# overview_mcu.net
KiCad netlist of a schematic drawn in EAGLE
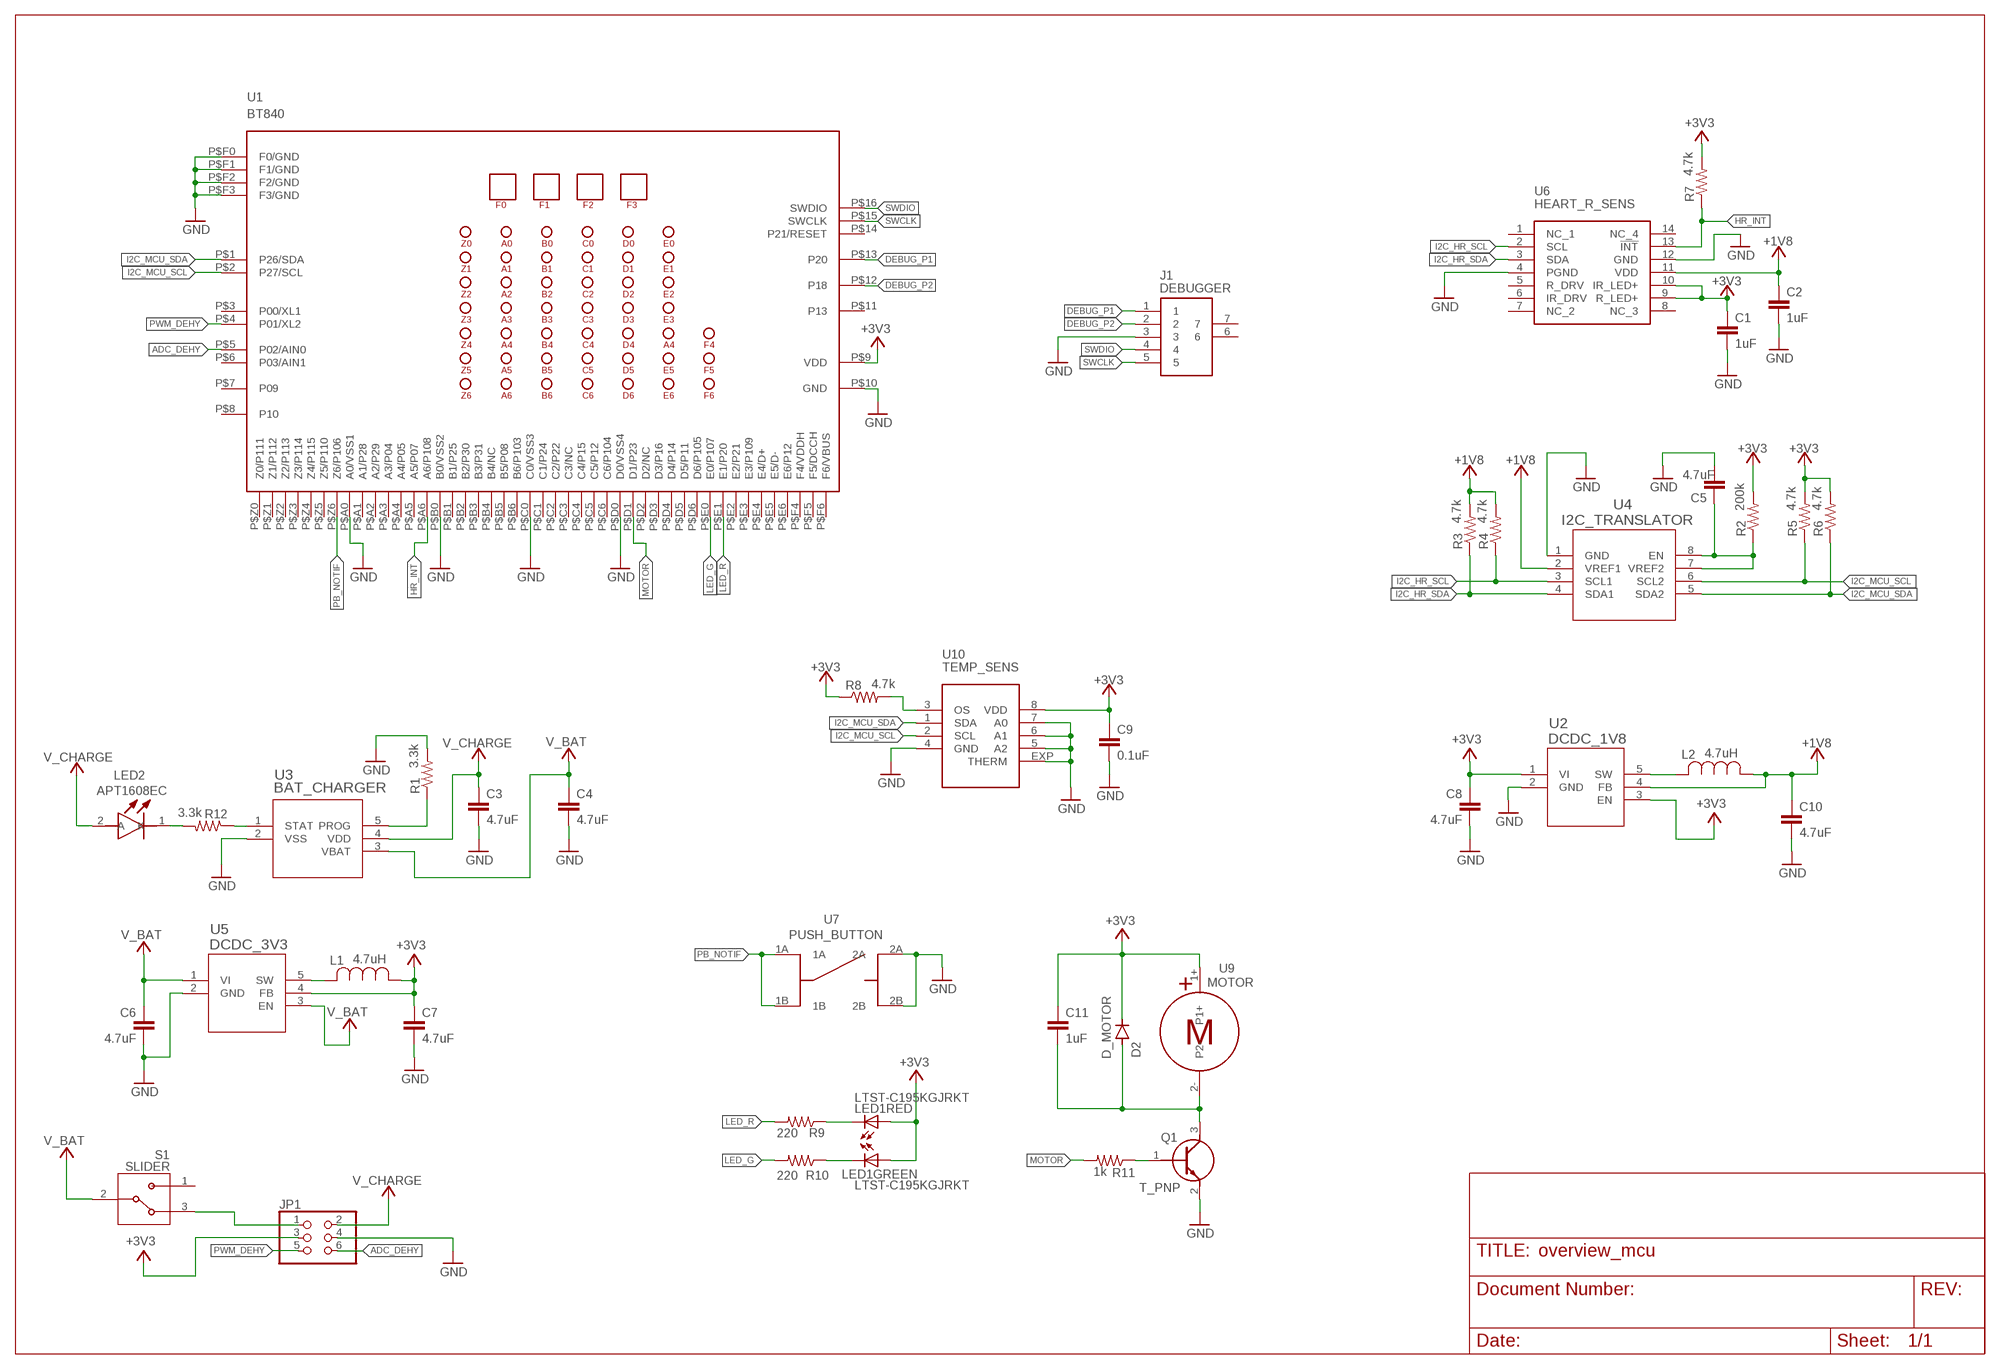
[diagram p0: schematic, sheet 1]

(export (version "E")
  (design (tool "Eeschema 10.0.6"))
  (components
    (comp (ref "C1")
      (value "1uF")
      (footprint "eagle-import:C0402K")
      (libsource (lib "eagle-import") (part "C-EUC0402K"))
    )
    (comp (ref "C2")
      (value "1uF")
      (footprint "eagle-import:C0402K")
      (libsource (lib "eagle-import") (part "C-EUC0402K"))
    )
    (comp (ref "C3")
      (value "4.7uF")
      (footprint "eagle-import:C0402K")
      (libsource (lib "eagle-import") (part "C-EUC0402K"))
    )
    (comp (ref "C4")
      (value "4.7uF")
      (footprint "eagle-import:C0402K")
      (libsource (lib "eagle-import") (part "C-EUC0402K"))
    )
    (comp (ref "C5")
      (value "4.7uF")
      (footprint "eagle-import:C0402K")
      (libsource (lib "eagle-import") (part "C-EUC0402K"))
    )
    (comp (ref "C6")
      (value "4.7uF")
      (footprint "eagle-import:C0402K")
      (libsource (lib "eagle-import") (part "C-EUC0402K"))
    )
    (comp (ref "C7")
      (value "4.7uF")
      (footprint "eagle-import:C0402K")
      (libsource (lib "eagle-import") (part "C-EUC0402K"))
    )
    (comp (ref "C8")
      (value "4.7uF")
      (footprint "eagle-import:C0402K")
      (libsource (lib "eagle-import") (part "C-EUC0402K"))
    )
    (comp (ref "C9")
      (value "0.1uF")
      (footprint "eagle-import:C0402K")
      (libsource (lib "eagle-import") (part "C-EUC0402K"))
    )
    (comp (ref "C10")
      (value "4.7uF")
      (footprint "eagle-import:C0402K")
      (libsource (lib "eagle-import") (part "C-EUC0402K"))
    )
    (comp (ref "C11")
      (value "1uF")
      (footprint "eagle-import:C0402K")
      (libsource (lib "eagle-import") (part "C-EUC0402K"))
    )
    (comp (ref "D2")
      (value "D_MOTOR")
      (footprint "eagle-import:SOD-123_MINI-SMA")
      (libsource (lib "eagle-import") (part "CGRM400-G1"))
    )
    (comp (ref "J1")
      (value "DEBUGGER")
      (footprint "eagle-import:0512810594")
      (fields (field (name "MANUFACTURER_PART_NUM") "0512810594"))
      (libsource (lib "eagle-import") (part "DEBUGGER"))
    )
    (comp (ref "JP1")
      (value "PINHD-2X3")
      (footprint "eagle-import:2X03")
      (libsource (lib "eagle-import") (part "PINHD-2X3"))
    )
    (comp (ref "L1")
      (value "4.7uH")
      (footprint "eagle-import:IND_1608")
      (fields (field (name "MANUFACTURER_PART_NUMBER") "GLFR1608T4R7MLR"))
      (libsource (lib "eagle-import") (part "L_0604"))
    )
    (comp (ref "L2")
      (value "4.7uH")
      (footprint "eagle-import:IND_1608")
      (fields (field (name "MANUFACTURER_PART_NUMBER") "GLFR1608T4R7MLR"))
      (libsource (lib "eagle-import") (part "L_0604"))
    )
    (comp (ref "LED1")
      (value "LTST-C195KGJRKT")
      (footprint "eagle-import:LED-SMT")
      (fields
        (field (name "MANUFACTURER") "Lite-On Inc.")
        (field (name "MANUFACTURER_PART_NUM") "LTST-C195KGJRKT ")
      )
      (libsource (lib "eagle-import") (part "LTST-C195KGJRKT"))
    )
    (comp (ref "LED2")
      (value "APT1608EC")
      (footprint "eagle-import:LEDC1608X85N")
      (fields (field (name "MANUFACTURER") "Kingbright"))
      (libsource (lib "eagle-import") (part "APT1608EC"))
    )
    (comp (ref "Q1")
      (value "T_PNP")
      (footprint "eagle-import:SOT95P240X93-3N")
      (fields
        (field (name "MANUFACTURER") "Micro Commercial Co")
        (field (name "MANUFACTURER_PART_NUM") "MMBT3904-TP ")
      )
      (libsource (lib "eagle-import") (part "T_PNP"))
    )
    (comp (ref "R1")
      (value "3.3k")
      (footprint "eagle-import:R0402")
      (libsource (lib "eagle-import") (part "R-US_R0402"))
    )
    (comp (ref "R2")
      (value "200k")
      (footprint "eagle-import:R0402")
      (libsource (lib "eagle-import") (part "R-US_R0402"))
    )
    (comp (ref "R3")
      (value "4.7k")
      (footprint "eagle-import:R0402")
      (libsource (lib "eagle-import") (part "R-US_R0402"))
    )
    (comp (ref "R4")
      (value "4.7k")
      (footprint "eagle-import:R0402")
      (libsource (lib "eagle-import") (part "R-US_R0402"))
    )
    (comp (ref "R5")
      (value "4.7k")
      (footprint "eagle-import:R0402")
      (libsource (lib "eagle-import") (part "R-US_R0402"))
    )
    (comp (ref "R6")
      (value "4.7k")
      (footprint "eagle-import:R0402")
      (libsource (lib "eagle-import") (part "R-US_R0402"))
    )
    (comp (ref "R7")
      (value "4.7k")
      (footprint "eagle-import:R0402")
      (libsource (lib "eagle-import") (part "R-US_R0402"))
    )
    (comp (ref "R8")
      (value "4.7k")
      (footprint "eagle-import:R0402")
      (libsource (lib "eagle-import") (part "R-US_R0402"))
    )
    (comp (ref "R9")
      (value "220")
      (footprint "eagle-import:R0402")
      (libsource (lib "eagle-import") (part "R-US_R0402"))
    )
    (comp (ref "R10")
      (value "220")
      (footprint "eagle-import:R0402")
      (libsource (lib "eagle-import") (part "R-US_R0402"))
    )
    (comp (ref "R11")
      (value "1k")
      (footprint "eagle-import:R0402")
      (libsource (lib "eagle-import") (part "R-US_R0402"))
    )
    (comp (ref "R12")
      (value "3.3k")
      (footprint "eagle-import:R0402")
      (libsource (lib "eagle-import") (part "R-US_R0402"))
    )
    (comp (ref "S1")
      (value "SLIDER")
      (footprint "eagle-import:SW_CJS-1200TA")
      (fields
        (field (name "MANUFACTURER") "Nidec Copal Electronics")
        (field (name "MANUFACTURER_PART") "CJS-1200TA ")
      )
      (libsource (lib "eagle-import") (part "SLIDER"))
    )
    (comp (ref "U1")
      (value "BT840")
      (footprint "eagle-import:BT840")
      (fields (field (name "MANUFACTURER") "Fanstel"))
      (libsource (lib "eagle-import") (part "BT840"))
    )
    (comp (ref "U2")
      (value "DCDC_1V8")
      (footprint "eagle-import:DBV5")
      (fields
        (field (name "MANUFACTURER") "Texas Instruments")
        (field (name "MANUFACTURER_PART_NUM") "TPS62202DBVR")
      )
      (libsource (lib "eagle-import") (part "DCDC_1V8"))
    )
    (comp (ref "U3")
      (value "BAT_CHARGER")
      (footprint "eagle-import:SOT-23-5_MC")
      (fields
        (field (name "MANUFACTURER") "Microchip")
        (field (name "MANUFACTURER_PART_NUM") "MCP73831T2ACIOT")
      )
      (libsource (lib "eagle-import") (part "BAT_CHARGER"))
    )
    (comp (ref "U4")
      (value "I2C_TRANSLATOR")
      (footprint "eagle-import:DQE8")
      (fields
        (field (name "MANUFACTURER") "Texas Instruments")
        (field (name "MANUFACTURER_PART_NUM") "PCA9306DQER")
      )
      (libsource (lib "eagle-import") (part "I2C_TRANSLATOR"))
    )
    (comp (ref "U5")
      (value "DCDC_3V3")
      (footprint "eagle-import:DBV5")
      (fields
        (field (name "MANUFACTURER") "Texas Instruments")
        (field (name "MANUFACTURER_PART_NUM") "TPS62203DBVR")
      )
      (libsource (lib "eagle-import") (part "DCDC_3V3"))
    )
    (comp (ref "U6")
      (value "HEART_R_SENS")
      (footprint "eagle-import:MAX30102")
      (fields
        (field (name "MANUFACTURER") "Maxim Integrated")
        (field (name "MANUFACTURER_PART_NUM") "MAX30102EFD+")
      )
      (libsource (lib "eagle-import") (part "HEART_R_SENS"))
    )
    (comp (ref "U7")
      (value "PUSH_BUTTON")
      (footprint "eagle-import:PUSH_BUTTON")
      (fields
        (field (name "MANUFACTURER") " Panasonic Electronic Components")
        (field (name "MANUFACTURER_PART_NUM") "EVQ-P7A01P ")
      )
      (libsource (lib "eagle-import") (part "PUSH_BUTTON"))
    )
    (comp (ref "U9")
      (value "MOTOR")
      (footprint "eagle-import:MOTOR")
      (fields
        (field (name "MANUFACTURER") "Jinlong Machinery & Electronics, Inc.")
        (field (name "MANUFACTURER_PART_NUM") "Z4FC1B1301781")
      )
      (libsource (lib "eagle-import") (part "MOTOR"))
    )
    (comp (ref "U10")
      (value "TEMP_SENS")
      (footprint "eagle-import:MAX30205")
      (fields
        (field (name "MANUFACTURER") "Maxim Integrated")
        (field (name "MANUFACTURER_PART_NUM") "MAX30205MTA+")
      )
      (libsource (lib "eagle-import") (part "TEMP_SENS"))
    )
  )
  (nets
    (net (code "1") (name "+1V8") (class "Default")
      (node (ref "C10") (pin "1") (pinfunction "1_1") (pintype "passive"))
      (node (ref "C2") (pin "1") (pinfunction "1_1") (pintype "passive"))
      (node (ref "L2") (pin "1") (pinfunction "1_1") (pintype "passive"))
      (node (ref "R3") (pin "2") (pinfunction "2_2") (pintype "passive"))
      (node (ref "R4") (pin "2") (pinfunction "2_2") (pintype "passive"))
      (node (ref "U2") (pin "4") (pinfunction "FB_4") (pintype "input"))
      (node (ref "U4") (pin "2") (pinfunction "VREF1_2") (pintype "passive"))
      (node (ref "U6") (pin "11") (pinfunction "VDD_11") (pintype "bidirectional"))
    )
    (net (code "2") (name "+3V3") (class "Default")
      (node (ref "C1") (pin "1") (pinfunction "1_1") (pintype "passive"))
      (node (ref "C11") (pin "1") (pinfunction "1_1") (pintype "passive"))
      (node (ref "C7") (pin "1") (pinfunction "1_1") (pintype "passive"))
      (node (ref "C8") (pin "1") (pinfunction "1_1") (pintype "passive"))
      (node (ref "C9") (pin "1") (pinfunction "1_1") (pintype "passive"))
      (node (ref "D2") (pin "C") (pinfunction "C_C") (pintype "passive"))
      (node (ref "JP1") (pin "3") (pinfunction "3_3") (pintype "passive"))
      (node (ref "L1") (pin "1") (pinfunction "1_1") (pintype "passive"))
      (node (ref "LED1") (pin "P$1") (pinfunction "A_P$1") (pintype "passive"))
      (node (ref "LED1") (pin "P$2") (pinfunction "A_P$2") (pintype "passive"))
      (node (ref "R2") (pin "2") (pinfunction "2_2") (pintype "passive"))
      (node (ref "R5") (pin "2") (pinfunction "2_2") (pintype "passive"))
      (node (ref "R6") (pin "2") (pinfunction "2_2") (pintype "passive"))
      (node (ref "R7") (pin "2") (pinfunction "2_2") (pintype "passive"))
      (node (ref "R8") (pin "1") (pinfunction "1_1") (pintype "passive"))
      (node (ref "U1") (pin "P$9") (pinfunction "VDD_P$9") (pintype "bidirectional"))
      (node (ref "U10") (pin "8") (pinfunction "VDD_8") (pintype "bidirectional"))
      (node (ref "U2") (pin "1") (pinfunction "VI_1") (pintype "input"))
      (node (ref "U2") (pin "3") (pinfunction "EN_3") (pintype "input"))
      (node (ref "U5") (pin "4") (pinfunction "FB_4") (pintype "input"))
      (node (ref "U6") (pin "10") (pinfunction "IR_LED+_10") (pintype "bidirectional"))
      (node (ref "U6") (pin "9") (pinfunction "R_LED+_9") (pintype "bidirectional"))
      (node (ref "U9") (pin "1+") (pinfunction "P1+_1+") (pintype "bidirectional"))
    )
    (net (code "3") (name "ADC_DEHY") (class "Default")
      (node (ref "JP1") (pin "6") (pinfunction "6_6") (pintype "passive"))
      (node (ref "U1") (pin "P$5") (pinfunction "P02/AIN0_P$5") (pintype "bidirectional"))
    )
    (net (code "4") (name "DEBUG_P1") (class "Default")
      (node (ref "J1") (pin "1") (pinfunction "1_1") (pintype "bidirectional"))
      (node (ref "U1") (pin "P$13") (pinfunction "P20_P$13") (pintype "bidirectional"))
    )
    (net (code "5") (name "DEBUG_P2") (class "Default")
      (node (ref "J1") (pin "2") (pinfunction "2_2") (pintype "bidirectional"))
      (node (ref "U1") (pin "P$12") (pinfunction "P18_P$12") (pintype "bidirectional"))
    )
    (net (code "6") (name "GND") (class "Default")
      (node (ref "C1") (pin "2") (pinfunction "2_2") (pintype "passive"))
      (node (ref "C10") (pin "2") (pinfunction "2_2") (pintype "passive"))
      (node (ref "C2") (pin "2") (pinfunction "2_2") (pintype "passive"))
      (node (ref "C3") (pin "2") (pinfunction "2_2") (pintype "passive"))
      (node (ref "C4") (pin "2") (pinfunction "2_2") (pintype "passive"))
      (node (ref "C5") (pin "2") (pinfunction "2_2") (pintype "passive"))
      (node (ref "C6") (pin "2") (pinfunction "2_2") (pintype "passive"))
      (node (ref "C7") (pin "2") (pinfunction "2_2") (pintype "passive"))
      (node (ref "C8") (pin "2") (pinfunction "2_2") (pintype "passive"))
      (node (ref "C9") (pin "2") (pinfunction "2_2") (pintype "passive"))
      (node (ref "J1") (pin "3") (pinfunction "3_3") (pintype "bidirectional"))
      (node (ref "JP1") (pin "4") (pinfunction "4_4") (pintype "passive"))
      (node (ref "Q1") (pin "2") (pinfunction "E_2") (pintype "bidirectional"))
      (node (ref "R1") (pin "2") (pinfunction "2_2") (pintype "passive"))
      (node (ref "U1") (pin "P$10") (pinfunction "GND_P$10") (pintype "bidirectional"))
      (node (ref "U1") (pin "P$A0") (pinfunction "A0/VSS1_P$A0") (pintype "bidirectional"))
      (node (ref "U1") (pin "P$B0") (pinfunction "B0/VSS2_P$B0") (pintype "bidirectional"))
      (node (ref "U1") (pin "P$C0") (pinfunction "C0/VSS3_P$C0") (pintype "bidirectional"))
      (node (ref "U1") (pin "P$D0") (pinfunction "D0/VSS4_P$D0") (pintype "bidirectional"))
      (node (ref "U1") (pin "P$F0") (pinfunction "F0/GND_P$F0") (pintype "bidirectional"))
      (node (ref "U1") (pin "P$F1") (pinfunction "F1/GND_P$F1") (pintype "bidirectional"))
      (node (ref "U1") (pin "P$F2") (pinfunction "F2/GND_P$F2") (pintype "bidirectional"))
      (node (ref "U1") (pin "P$F3") (pinfunction "F3/GND_P$F3") (pintype "bidirectional"))
      (node (ref "U10") (pin "4") (pinfunction "GND_4") (pintype "bidirectional"))
      (node (ref "U10") (pin "5") (pinfunction "A2_5") (pintype "bidirectional"))
      (node (ref "U10") (pin "6") (pinfunction "A1_6") (pintype "bidirectional"))
      (node (ref "U10") (pin "7") (pinfunction "A0_7") (pintype "bidirectional"))
      (node (ref "U10") (pin "EXP") (pinfunction "THERM_EXP") (pintype "bidirectional"))
      (node (ref "U2") (pin "2") (pinfunction "GND_2") (pintype "power_in"))
      (node (ref "U3") (pin "2") (pinfunction "VSS_2") (pintype "passive"))
      (node (ref "U4") (pin "1") (pinfunction "GND_1") (pintype "power_in"))
      (node (ref "U5") (pin "2") (pinfunction "GND_2") (pintype "power_in"))
      (node (ref "U6") (pin "12") (pinfunction "GND_12") (pintype "bidirectional"))
      (node (ref "U6") (pin "4") (pinfunction "PGND_4") (pintype "bidirectional"))
      (node (ref "U7") (pin "2A") (pinfunction "2A_2A") (pintype "bidirectional"))
      (node (ref "U7") (pin "2B") (pinfunction "2B_2B") (pintype "bidirectional"))
    )
    (net (code "7") (name "HR_INT") (class "Default")
      (node (ref "R7") (pin "1") (pinfunction "1_1") (pintype "passive"))
      (node (ref "U1") (pin "P$A6") (pinfunction "A6/P108_P$A6") (pintype "bidirectional"))
      (node (ref "U6") (pin "13") (pinfunction "~{INT}_13") (pintype "bidirectional"))
    )
    (net (code "8") (name "I2C_HR_SCL") (class "Default")
      (node (ref "R4") (pin "1") (pinfunction "1_1") (pintype "passive"))
      (node (ref "U4") (pin "3") (pinfunction "SCL1_3") (pintype "passive"))
      (node (ref "U6") (pin "2") (pinfunction "SCL_2") (pintype "bidirectional"))
    )
    (net (code "9") (name "I2C_HR_SDA") (class "Default")
      (node (ref "R3") (pin "1") (pinfunction "1_1") (pintype "passive"))
      (node (ref "U4") (pin "4") (pinfunction "SDA1_4") (pintype "passive"))
      (node (ref "U6") (pin "3") (pinfunction "SDA_3") (pintype "bidirectional"))
    )
    (net (code "10") (name "I2C_MCU_SCL") (class "Default")
      (node (ref "R5") (pin "1") (pinfunction "1_1") (pintype "passive"))
      (node (ref "U1") (pin "P$2") (pinfunction "P27/SCL_P$2") (pintype "bidirectional"))
      (node (ref "U10") (pin "2") (pinfunction "SCL_2") (pintype "bidirectional"))
      (node (ref "U4") (pin "6") (pinfunction "SCL2_6") (pintype "passive"))
    )
    (net (code "11") (name "I2C_MCU_SDA") (class "Default")
      (node (ref "R6") (pin "1") (pinfunction "1_1") (pintype "passive"))
      (node (ref "U1") (pin "P$1") (pinfunction "P26/SDA_P$1") (pintype "bidirectional"))
      (node (ref "U10") (pin "1") (pinfunction "SDA_1") (pintype "bidirectional"))
      (node (ref "U4") (pin "5") (pinfunction "SDA2_5") (pintype "passive"))
    )
    (net (code "12") (name "LED_G") (class "Default")
      (node (ref "R10") (pin "2") (pinfunction "2_2") (pintype "passive"))
      (node (ref "U1") (pin "P$E0") (pinfunction "E0/P107_P$E0") (pintype "bidirectional"))
    )
    (net (code "13") (name "LED_R") (class "Default")
      (node (ref "R9") (pin "2") (pinfunction "2_2") (pintype "passive"))
      (node (ref "U1") (pin "P$E1") (pinfunction "E1/P20_P$E1") (pintype "bidirectional"))
    )
    (net (code "14") (name "MOTOR") (class "Default")
      (node (ref "R11") (pin "2") (pinfunction "2_2") (pintype "passive"))
      (node (ref "U1") (pin "P$D1") (pinfunction "D1/P23_P$D1") (pintype "bidirectional"))
    )
    (net (code "15") (name "Net-(JP1-Pad1)") (class "Default")
      (node (ref "JP1") (pin "1") (pinfunction "1_1") (pintype "passive"))
      (node (ref "S1") (pin "3") (pinfunction "3_3") (pintype "passive"))
    )
    (net (code "16") (name "Net-(LED1A-C)") (class "Default")
      (node (ref "LED1") (pin "P$3") (pinfunction "C_P$3") (pintype "passive"))
      (node (ref "R10") (pin "1") (pinfunction "1_1") (pintype "passive"))
    )
    (net (code "17") (name "Net-(LED1B-C)") (class "Default")
      (node (ref "LED1") (pin "P$4") (pinfunction "C_P$4") (pintype "passive"))
      (node (ref "R9") (pin "1") (pinfunction "1_1") (pintype "passive"))
    )
    (net (code "18") (name "Net-(LED2-K)") (class "Default")
      (node (ref "LED2") (pin "1") (pinfunction "K_1") (pintype "bidirectional"))
      (node (ref "R12") (pin "2") (pinfunction "2_2") (pintype "passive"))
    )
    (net (code "19") (name "Net-(Q1-B)") (class "Default")
      (node (ref "Q1") (pin "1") (pinfunction "B_1") (pintype "bidirectional"))
      (node (ref "R11") (pin "1") (pinfunction "1_1") (pintype "passive"))
    )
    (net (code "20") (name "Net-(Q1-C)") (class "Default")
      (node (ref "C11") (pin "2") (pinfunction "2_2") (pintype "passive"))
      (node (ref "D2") (pin "A") (pinfunction "A_A") (pintype "passive"))
      (node (ref "Q1") (pin "3") (pinfunction "C_3") (pintype "bidirectional"))
      (node (ref "U9") (pin "2-") (pinfunction "P2-_2-") (pintype "bidirectional"))
    )
    (net (code "21") (name "Net-(U2-SW)") (class "Default")
      (node (ref "L2") (pin "2") (pinfunction "2_2") (pintype "passive"))
      (node (ref "U2") (pin "5") (pinfunction "SW_5") (pintype "bidirectional"))
    )
    (net (code "22") (name "Net-(U3-PROG)") (class "Default")
      (node (ref "R1") (pin "1") (pinfunction "1_1") (pintype "passive"))
      (node (ref "U3") (pin "5") (pinfunction "PROG_5") (pintype "passive"))
    )
    (net (code "23") (name "Net-(U3-STAT)") (class "Default")
      (node (ref "R12") (pin "1") (pinfunction "1_1") (pintype "passive"))
      (node (ref "U3") (pin "1") (pinfunction "STAT_1") (pintype "passive"))
    )
    (net (code "24") (name "Net-(U4-EN)") (class "Default")
      (node (ref "C5") (pin "1") (pinfunction "1_1") (pintype "passive"))
      (node (ref "R2") (pin "1") (pinfunction "1_1") (pintype "passive"))
      (node (ref "U4") (pin "7") (pinfunction "VREF2_7") (pintype "passive"))
      (node (ref "U4") (pin "8") (pinfunction "EN_8") (pintype "passive"))
    )
    (net (code "25") (name "Net-(U5-SW)") (class "Default")
      (node (ref "L1") (pin "2") (pinfunction "2_2") (pintype "passive"))
      (node (ref "U5") (pin "5") (pinfunction "SW_5") (pintype "bidirectional"))
    )
    (net (code "26") (name "Net-(U10-OS)") (class "Default")
      (node (ref "R8") (pin "2") (pinfunction "2_2") (pintype "passive"))
      (node (ref "U10") (pin "3") (pinfunction "OS_3") (pintype "bidirectional"))
    )
    (net (code "27") (name "PB_NOTIF") (class "Default")
      (node (ref "U1") (pin "P$Z6") (pinfunction "Z6/P106_P$Z6") (pintype "bidirectional"))
      (node (ref "U7") (pin "1A") (pinfunction "1A_1A") (pintype "bidirectional"))
      (node (ref "U7") (pin "1B") (pinfunction "1B_1B") (pintype "bidirectional"))
    )
    (net (code "28") (name "PWM_DEHY") (class "Default")
      (node (ref "JP1") (pin "5") (pinfunction "5_5") (pintype "passive"))
      (node (ref "U1") (pin "P$4") (pinfunction "P01/XL2_P$4") (pintype "bidirectional"))
    )
    (net (code "29") (name "SWCLK") (class "Default")
      (node (ref "J1") (pin "5") (pinfunction "5_5") (pintype "bidirectional"))
      (node (ref "U1") (pin "P$15") (pinfunction "SWCLK_P$15") (pintype "bidirectional"))
    )
    (net (code "30") (name "SWDIO") (class "Default")
      (node (ref "J1") (pin "4") (pinfunction "4_4") (pintype "bidirectional"))
      (node (ref "U1") (pin "P$16") (pinfunction "SWDIO_P$16") (pintype "bidirectional"))
    )
    (net (code "31") (name "V_BAT") (class "Default")
      (node (ref "C4") (pin "1") (pinfunction "1_1") (pintype "passive"))
      (node (ref "C6") (pin "1") (pinfunction "1_1") (pintype "passive"))
      (node (ref "S1") (pin "2") (pinfunction "2_2") (pintype "passive"))
      (node (ref "U3") (pin "3") (pinfunction "VBAT_3") (pintype "passive"))
      (node (ref "U5") (pin "1") (pinfunction "VI_1") (pintype "input"))
      (node (ref "U5") (pin "3") (pinfunction "EN_3") (pintype "input"))
    )
    (net (code "32") (name "V_CHARGE") (class "Default")
      (node (ref "C3") (pin "1") (pinfunction "1_1") (pintype "passive"))
      (node (ref "JP1") (pin "2") (pinfunction "2_2") (pintype "passive"))
      (node (ref "LED2") (pin "2") (pinfunction "A_2") (pintype "bidirectional"))
      (node (ref "U3") (pin "4") (pinfunction "VDD_4") (pintype "passive"))
    )
    (net (code "33") (name "unconnected-(J1-Pad6)") (class "Default")
      (node (ref "J1") (pin "6") (pinfunction "6_6") (pintype "bidirectional"))
    )
    (net (code "34") (name "unconnected-(J1-Pad7)") (class "Default")
      (node (ref "J1") (pin "7") (pinfunction "7_7") (pintype "bidirectional"))
    )
    (net (code "35") (name "unconnected-(S1-Pad1)") (class "Default")
      (node (ref "S1") (pin "1") (pinfunction "1_1") (pintype "passive"))
    )
    (net (code "36") (name "unconnected-(U1-A1{slash}P28-PadP$A1)") (class "Default")
      (node (ref "U1") (pin "P$A1") (pinfunction "A1/P28_P$A1") (pintype "bidirectional"))
    )
    (net (code "37") (name "unconnected-(U1-A2{slash}P29-PadP$A2)") (class "Default")
      (node (ref "U1") (pin "P$A2") (pinfunction "A2/P29_P$A2") (pintype "bidirectional"))
    )
    (net (code "38") (name "unconnected-(U1-A3{slash}P04-PadP$A3)") (class "Default")
      (node (ref "U1") (pin "P$A3") (pinfunction "A3/P04_P$A3") (pintype "bidirectional"))
    )
    (net (code "39") (name "unconnected-(U1-A4{slash}P05-PadP$A4)") (class "Default")
      (node (ref "U1") (pin "P$A4") (pinfunction "A4/P05_P$A4") (pintype "bidirectional"))
    )
    (net (code "40") (name "unconnected-(U1-A5{slash}P07-PadP$A5)") (class "Default")
      (node (ref "U1") (pin "P$A5") (pinfunction "A5/P07_P$A5") (pintype "bidirectional"))
    )
    (net (code "41") (name "unconnected-(U1-B1{slash}P25-PadP$B1)") (class "Default")
      (node (ref "U1") (pin "P$B1") (pinfunction "B1/P25_P$B1") (pintype "bidirectional"))
    )
    (net (code "42") (name "unconnected-(U1-B2{slash}P30-PadP$B2)") (class "Default")
      (node (ref "U1") (pin "P$B2") (pinfunction "B2/P30_P$B2") (pintype "bidirectional"))
    )
    (net (code "43") (name "unconnected-(U1-B3{slash}P31-PadP$B3)") (class "Default")
      (node (ref "U1") (pin "P$B3") (pinfunction "B3/P31_P$B3") (pintype "bidirectional"))
    )
    (net (code "44") (name "unconnected-(U1-B4{slash}NC-PadP$B4)") (class "Default")
      (node (ref "U1") (pin "P$B4") (pinfunction "B4/NC_P$B4") (pintype "bidirectional"))
    )
    (net (code "45") (name "unconnected-(U1-B5{slash}P08-PadP$B5)") (class "Default")
      (node (ref "U1") (pin "P$B5") (pinfunction "B5/P08_P$B5") (pintype "bidirectional"))
    )
    (net (code "46") (name "unconnected-(U1-B6{slash}P103-PadP$B6)") (class "Default")
      (node (ref "U1") (pin "P$B6") (pinfunction "B6/P103_P$B6") (pintype "bidirectional"))
    )
    (net (code "47") (name "unconnected-(U1-C1{slash}P24-PadP$C1)") (class "Default")
      (node (ref "U1") (pin "P$C1") (pinfunction "C1/P24_P$C1") (pintype "bidirectional"))
    )
    (net (code "48") (name "unconnected-(U1-C2{slash}P22-PadP$C2)") (class "Default")
      (node (ref "U1") (pin "P$C2") (pinfunction "C2/P22_P$C2") (pintype "bidirectional"))
    )
    (net (code "49") (name "unconnected-(U1-C3{slash}NC-PadP$C3)") (class "Default")
      (node (ref "U1") (pin "P$C3") (pinfunction "C3/NC_P$C3") (pintype "bidirectional"))
    )
    (net (code "50") (name "unconnected-(U1-C4{slash}P15-PadP$C4)") (class "Default")
      (node (ref "U1") (pin "P$C4") (pinfunction "C4/P15_P$C4") (pintype "bidirectional"))
    )
    (net (code "51") (name "unconnected-(U1-C5{slash}P12-PadP$C5)") (class "Default")
      (node (ref "U1") (pin "P$C5") (pinfunction "C5/P12_P$C5") (pintype "bidirectional"))
    )
    (net (code "52") (name "unconnected-(U1-C6{slash}P104-PadP$C6)") (class "Default")
      (node (ref "U1") (pin "P$C6") (pinfunction "C6/P104_P$C6") (pintype "bidirectional"))
    )
    (net (code "53") (name "unconnected-(U1-D2{slash}NC-PadP$D2)") (class "Default")
      (node (ref "U1") (pin "P$D2") (pinfunction "D2/NC_P$D2") (pintype "bidirectional"))
    )
    (net (code "54") (name "unconnected-(U1-D3{slash}P16-PadP$D3)") (class "Default")
      (node (ref "U1") (pin "P$D3") (pinfunction "D3/P16_P$D3") (pintype "bidirectional"))
    )
    (net (code "55") (name "unconnected-(U1-D4{slash}P14-PadP$D4)") (class "Default")
      (node (ref "U1") (pin "P$D4") (pinfunction "D4/P14_P$D4") (pintype "bidirectional"))
    )
    (net (code "56") (name "unconnected-(U1-D5{slash}P11-PadP$D5)") (class "Default")
      (node (ref "U1") (pin "P$D5") (pinfunction "D5/P11_P$D5") (pintype "bidirectional"))
    )
    (net (code "57") (name "unconnected-(U1-D6{slash}P105-PadP$D6)") (class "Default")
      (node (ref "U1") (pin "P$D6") (pinfunction "D6/P105_P$D6") (pintype "bidirectional"))
    )
    (net (code "58") (name "unconnected-(U1-E2{slash}P21-PadP$E2)") (class "Default")
      (node (ref "U1") (pin "P$E2") (pinfunction "E2/P21_P$E2") (pintype "bidirectional"))
    )
    (net (code "59") (name "unconnected-(U1-E3{slash}P109-PadP$E3)") (class "Default")
      (node (ref "U1") (pin "P$E3") (pinfunction "E3/P109_P$E3") (pintype "bidirectional"))
    )
    (net (code "60") (name "unconnected-(U1-E4{slash}D+-PadP$E4)") (class "Default")
      (node (ref "U1") (pin "P$E4") (pinfunction "E4/D+_P$E4") (pintype "bidirectional"))
    )
    (net (code "61") (name "unconnected-(U1-E5{slash}D--PadP$E5)") (class "Default")
      (node (ref "U1") (pin "P$E5") (pinfunction "E5/D-_P$E5") (pintype "bidirectional"))
    )
    (net (code "62") (name "unconnected-(U1-E6{slash}P12-PadP$E6)") (class "Default")
      (node (ref "U1") (pin "P$E6") (pinfunction "E6/P12_P$E6") (pintype "bidirectional"))
    )
    (net (code "63") (name "unconnected-(U1-F4{slash}VDDH-PadP$F4)") (class "Default")
      (node (ref "U1") (pin "P$F4") (pinfunction "F4/VDDH_P$F4") (pintype "bidirectional"))
    )
    (net (code "64") (name "unconnected-(U1-F5{slash}DCCH-PadP$F5)") (class "Default")
      (node (ref "U1") (pin "P$F5") (pinfunction "F5/DCCH_P$F5") (pintype "bidirectional"))
    )
    (net (code "65") (name "unconnected-(U1-F6{slash}VBUS-PadP$F6)") (class "Default")
      (node (ref "U1") (pin "P$F6") (pinfunction "F6/VBUS_P$F6") (pintype "bidirectional"))
    )
    (net (code "66") (name "unconnected-(U1-P00{slash}XL1-PadP$3)") (class "Default")
      (node (ref "U1") (pin "P$3") (pinfunction "P00/XL1_P$3") (pintype "bidirectional"))
    )
    (net (code "67") (name "unconnected-(U1-P03{slash}AIN1-PadP$6)") (class "Default")
      (node (ref "U1") (pin "P$6") (pinfunction "P03/AIN1_P$6") (pintype "bidirectional"))
    )
    (net (code "68") (name "unconnected-(U1-P09-PadP$7)") (class "Default")
      (node (ref "U1") (pin "P$7") (pinfunction "P09_P$7") (pintype "bidirectional"))
    )
    (net (code "69") (name "unconnected-(U1-P10-PadP$8)") (class "Default")
      (node (ref "U1") (pin "P$8") (pinfunction "P10_P$8") (pintype "bidirectional"))
    )
    (net (code "70") (name "unconnected-(U1-P13-PadP$11)") (class "Default")
      (node (ref "U1") (pin "P$11") (pinfunction "P13_P$11") (pintype "bidirectional"))
    )
    (net (code "71") (name "unconnected-(U1-P21{slash}RESET-PadP$14)") (class "Default")
      (node (ref "U1") (pin "P$14") (pinfunction "P21/RESET_P$14") (pintype "bidirectional"))
    )
    (net (code "72") (name "unconnected-(U1-Z0{slash}P111-PadP$Z0)") (class "Default")
      (node (ref "U1") (pin "P$Z0") (pinfunction "Z0/P111_P$Z0") (pintype "bidirectional"))
    )
    (net (code "73") (name "unconnected-(U1-Z1{slash}P112-PadP$Z1)") (class "Default")
      (node (ref "U1") (pin "P$Z1") (pinfunction "Z1/P112_P$Z1") (pintype "bidirectional"))
    )
    (net (code "74") (name "unconnected-(U1-Z2{slash}P113-PadP$Z2)") (class "Default")
      (node (ref "U1") (pin "P$Z2") (pinfunction "Z2/P113_P$Z2") (pintype "bidirectional"))
    )
    (net (code "75") (name "unconnected-(U1-Z3{slash}P114-PadP$Z3)") (class "Default")
      (node (ref "U1") (pin "P$Z3") (pinfunction "Z3/P114_P$Z3") (pintype "bidirectional"))
    )
    (net (code "76") (name "unconnected-(U1-Z4{slash}P115-PadP$Z4)") (class "Default")
      (node (ref "U1") (pin "P$Z4") (pinfunction "Z4/P115_P$Z4") (pintype "bidirectional"))
    )
    (net (code "77") (name "unconnected-(U1-Z5{slash}P110-PadP$Z5)") (class "Default")
      (node (ref "U1") (pin "P$Z5") (pinfunction "Z5/P110_P$Z5") (pintype "bidirectional"))
    )
    (net (code "78") (name "unconnected-(U6-IR_DRV-Pad6)") (class "Default")
      (node (ref "U6") (pin "6") (pinfunction "IR_DRV_6") (pintype "bidirectional"))
    )
    (net (code "79") (name "unconnected-(U6-NC_1-Pad1)") (class "Default")
      (node (ref "U6") (pin "1") (pinfunction "NC_1_1") (pintype "bidirectional"))
    )
    (net (code "80") (name "unconnected-(U6-NC_2-Pad7)") (class "Default")
      (node (ref "U6") (pin "7") (pinfunction "NC_2_7") (pintype "bidirectional"))
    )
    (net (code "81") (name "unconnected-(U6-NC_3-Pad8)") (class "Default")
      (node (ref "U6") (pin "8") (pinfunction "NC_3_8") (pintype "bidirectional"))
    )
    (net (code "82") (name "unconnected-(U6-NC_4-Pad14)") (class "Default")
      (node (ref "U6") (pin "14") (pinfunction "NC_4_14") (pintype "bidirectional"))
    )
    (net (code "83") (name "unconnected-(U6-R_DRV-Pad5)") (class "Default")
      (node (ref "U6") (pin "5") (pinfunction "R_DRV_5") (pintype "bidirectional"))
    )
  )
)
